# Charger_MCU_V01.net
KiCad netlist of a schematic drawn in Altium Designer
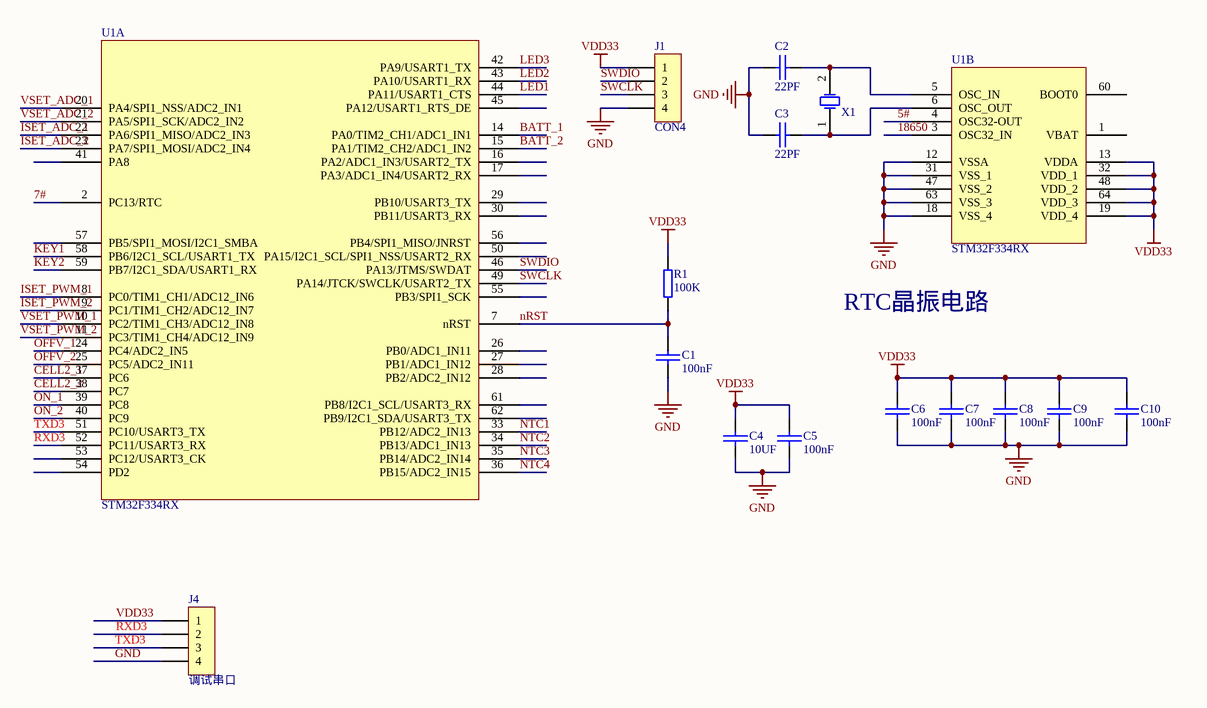
[diagram p0: Charger_MCU_V01.SchDoc]

(export (version "E")
  (design (tool "Eeschema 10.0.6"))
  (components
    (comp (ref "C1")
      (value "100nF")
      (footprint "C0603")
      (description "CAP CER 0.1UF 50V Y5V 0603")
      (fields
        (field (name "MANUFACTURER") "Yageo")
        (field (name "MANUFACTURER PART NUMBER") "CC0603ZRY5V9BB104")
      )
      (libsource (lib "电容") (part "C0603"))
    )
    (comp (ref "C2")
      (value "22PF")
      (footprint "C0603")
      (description "CAP CER 22PF 50V Y5V 0603")
      (fields (field (name "Comment") "C0603"))
      (libsource (lib "电容") (part "C0603"))
    )
    (comp (ref "C3")
      (value "22PF")
      (footprint "C0603")
      (description "CAP CER 22PF 50V Y5V 0603")
      (fields (field (name "Comment") "C0603"))
      (libsource (lib "电容") (part "C0603"))
    )
    (comp (ref "C4")
      (value "10UF")
      (footprint "C0603")
      (description "CAP CER 10UF 50V Y5V 0603")
      (fields
        (field (name "MANUFACTURER") "Yageo")
        (field (name "MANUFACTURER PART NUMBER") "CC0603ZRY5V9BB106")
      )
      (libsource (lib "电容") (part "C0603"))
    )
    (comp (ref "C5")
      (value "100nF")
      (footprint "C0603")
      (description "CAP CER 100nF 50V Y5V 0603")
      (fields
        (field (name "MANUFACTURER") "Yageo")
        (field (name "MANUFACTURER PART NUMBER") "CC0603ZRY5V9BB104")
      )
      (libsource (lib "电容") (part "C0603"))
    )
    (comp (ref "C6")
      (value "100nF")
      (footprint "C0603")
      (description "CAP CER 100nF 50V Y5V 0603")
      (fields
        (field (name "MANUFACTURER") "Yageo")
        (field (name "MANUFACTURER PART NUMBER") "CC0603ZRY5V9BB104")
      )
      (libsource (lib "电容") (part "C0603"))
    )
    (comp (ref "C7")
      (value "100nF")
      (footprint "C0603")
      (description "CAP CER 100nF 50V Y5V 0603")
      (fields
        (field (name "MANUFACTURER") "Yageo")
        (field (name "MANUFACTURER PART NUMBER") "CC0603ZRY5V9BB104")
      )
      (libsource (lib "电容") (part "C0603"))
    )
    (comp (ref "C8")
      (value "100nF")
      (footprint "C0603")
      (description "CAP CER 100nF 50V Y5V 0603")
      (fields
        (field (name "MANUFACTURER") "Yageo")
        (field (name "MANUFACTURER PART NUMBER") "CC0603ZRY5V9BB104")
      )
      (libsource (lib "电容") (part "C0603"))
    )
    (comp (ref "C9")
      (value "100nF")
      (footprint "C0603")
      (description "CAP CER 100nF 50V Y5V 0603")
      (fields
        (field (name "MANUFACTURER") "Yageo")
        (field (name "MANUFACTURER PART NUMBER") "CC0603ZRY5V9BB104")
      )
      (libsource (lib "电容") (part "C0603"))
    )
    (comp (ref "C10")
      (value "100nF")
      (footprint "C0603")
      (description "CAP CER 100nF 50V Y5V 0603")
      (fields
        (field (name "MANUFACTURER") "Yageo")
        (field (name "MANUFACTURER PART NUMBER") "CC0603ZRY5V9BB104")
      )
      (libsource (lib "电容") (part "C0603"))
    )
    (comp (ref "J1")
      (value "CON4")
      (footprint "SIP4")
      (description "2.54mm 程序下载口")
      (libsource (lib "") (part "CON4_1"))
    )
    (comp (ref "J4")
      (value "调试串口")
      (footprint "SIP4")
      (description "2.54mm dip")
      (libsource (lib "接插件") (part "CON4"))
    )
    (comp (ref "R1")
      (value "100K")
      (footprint "R0603")
      (description "RES 100K OHM 1/10W 5% 0603 SMD")
      (fields (field (name "MANUFACTURER") "Yageo") (field (name "Comment") "R0603"))
      (libsource (lib "电阻") (part "R0603"))
    )
    (comp (ref "U1")
      (value "STM32F334RX")
      (footprint "LQFP64")
      (description "MCU ARM 64KB FLASH MEM 64-LQFP")
      (fields
        (field (name "MANUFACTURER") "STMicroelectronics")
        (field (name "MANUFACTURER PART NUMBER") "STM32F103R8T6")
      )
      (libsource (lib "集成电路") (part "STM32F334RX"))
    )
    (comp (ref "X1")
      (value "9C-8.000MBBK-T")
      (footprint "XTAL2")
      (description "CRYSTAL 8.000MHZ 20PF SMD")
      (fields (field (name "MANUFACTURER") "TXC CORPORATION"))
      (libsource (lib "接插件") (part "CRYSTAL-XTAL2"))
    )
  )
  (nets
    (net (code "1") (name "/5#") (class "Default")
      (node (ref "U1") (pin "4") (pinfunction "OSC32-OUT_4") (pintype "passive"))
    )
    (net (code "2") (name "/7#") (class "Default")
      (node (ref "U1") (pin "2") (pinfunction "PC13/RTC_2") (pintype "passive"))
    )
    (net (code "3") (name "/18650") (class "Default")
      (node (ref "U1") (pin "3") (pinfunction "OSC32_IN_3") (pintype "passive"))
    )
    (net (code "4") (name "/BATT_1") (class "Default")
      (node (ref "U1") (pin "14") (pinfunction "PA0/TIM2_CH1/ADC1_IN1_14") (pintype "passive"))
    )
    (net (code "5") (name "/BATT_2") (class "Default")
      (node (ref "U1") (pin "15") (pinfunction "PA1/TIM2_CH2/ADC1_IN2_15") (pintype "passive"))
    )
    (net (code "6") (name "/CELL2_1") (class "Default")
      (node (ref "U1") (pin "37") (pinfunction "PC6_37") (pintype "passive"))
    )
    (net (code "7") (name "/CELL2_2") (class "Default")
      (node (ref "U1") (pin "38") (pinfunction "PC7_38") (pintype "passive"))
    )
    (net (code "8") (name "/ISET_ADC_1") (class "Default")
      (node (ref "U1") (pin "22") (pinfunction "PA6/SPI1_MISO/ADC2_IN3_22") (pintype "passive"))
    )
    (net (code "9") (name "/ISET_ADC_2") (class "Default")
      (node (ref "U1") (pin "23") (pinfunction "PA7/SPI1_MOSI/ADC2_IN4_23") (pintype "passive"))
    )
    (net (code "10") (name "/ISET_PWM_1") (class "Default")
      (node (ref "U1") (pin "8") (pinfunction "PC0/TIM1_CH1/ADC12_IN6_8") (pintype "passive"))
    )
    (net (code "11") (name "/ISET_PWM_2") (class "Default")
      (node (ref "U1") (pin "9") (pinfunction "PC1/TIM1_CH2/ADC12_IN7_9") (pintype "passive"))
    )
    (net (code "12") (name "/KEY1") (class "Default")
      (node (ref "U1") (pin "58") (pinfunction "PB6/I2C1_SCL/USART1_TX_58") (pintype "passive"))
    )
    (net (code "13") (name "/KEY2") (class "Default")
      (node (ref "U1") (pin "59") (pinfunction "PB7/I2C1_SDA/USART1_RX_59") (pintype "passive"))
    )
    (net (code "14") (name "/LED1") (class "Default")
      (node (ref "U1") (pin "44") (pinfunction "PA11/USART1_CTS_44") (pintype "passive"))
    )
    (net (code "15") (name "/LED2") (class "Default")
      (node (ref "U1") (pin "43") (pinfunction "PA10/USART1_RX_43") (pintype "passive"))
    )
    (net (code "16") (name "/LED3") (class "Default")
      (node (ref "U1") (pin "42") (pinfunction "PA9/USART1_TX_42") (pintype "passive"))
    )
    (net (code "17") (name "/NTC1") (class "Default")
      (node (ref "U1") (pin "33") (pinfunction "PB12/ADC2_IN13_33") (pintype "passive"))
    )
    (net (code "18") (name "/NTC2") (class "Default")
      (node (ref "U1") (pin "34") (pinfunction "PB13/ADC1_IN13_34") (pintype "passive"))
    )
    (net (code "19") (name "/NTC3") (class "Default")
      (node (ref "U1") (pin "35") (pinfunction "PB14/ADC2_IN14_35") (pintype "passive"))
    )
    (net (code "20") (name "/NTC4") (class "Default")
      (node (ref "U1") (pin "36") (pinfunction "PB15/ADC2_IN15_36") (pintype "passive"))
    )
    (net (code "21") (name "/OFFV_1") (class "Default")
      (node (ref "U1") (pin "24") (pinfunction "PC4/ADC2_IN5_24") (pintype "passive"))
    )
    (net (code "22") (name "/OFFV_2") (class "Default")
      (node (ref "U1") (pin "25") (pinfunction "PC5/ADC2_IN11_25") (pintype "passive"))
    )
    (net (code "23") (name "/ON_1") (class "Default")
      (node (ref "U1") (pin "39") (pinfunction "PC8_39") (pintype "passive"))
    )
    (net (code "24") (name "/ON_2") (class "Default")
      (node (ref "U1") (pin "40") (pinfunction "PC9_40") (pintype "passive"))
    )
    (net (code "25") (name "/RXD3") (class "Default")
      (node (ref "J4") (pin "2") (pinfunction "2_2") (pintype "passive"))
      (node (ref "U1") (pin "52") (pinfunction "PC11/USART3_RX_52") (pintype "passive"))
    )
    (net (code "26") (name "/SWCLK") (class "Default")
      (node (ref "J1") (pin "3") (pinfunction "3_3") (pintype "passive"))
      (node (ref "U1") (pin "49") (pinfunction "PA14/JTCK/SWCLK/USART2_TX_49") (pintype "passive"))
    )
    (net (code "27") (name "/SWDIO") (class "Default")
      (node (ref "J1") (pin "2") (pinfunction "2_2") (pintype "passive"))
      (node (ref "U1") (pin "46") (pinfunction "PA13/JTMS/SWDAT_46") (pintype "passive"))
    )
    (net (code "28") (name "/TXD3") (class "Default")
      (node (ref "J4") (pin "3") (pinfunction "3_3") (pintype "passive"))
      (node (ref "U1") (pin "51") (pinfunction "PC10/USART3_TX_51") (pintype "passive"))
    )
    (net (code "29") (name "/VSET_ADC_1") (class "Default")
      (node (ref "U1") (pin "20") (pinfunction "PA4/SPI1_NSS/ADC2_IN1_20") (pintype "passive"))
    )
    (net (code "30") (name "/VSET_ADC_2") (class "Default")
      (node (ref "U1") (pin "21") (pinfunction "PA5/SPI1_SCK/ADC2_IN2_21") (pintype "passive"))
    )
    (net (code "31") (name "/VSET_PWM_1") (class "Default")
      (node (ref "U1") (pin "10") (pinfunction "PC2/TIM1_CH3/ADC12_IN8_10") (pintype "passive"))
    )
    (net (code "32") (name "/VSET_PWM_2") (class "Default")
      (node (ref "U1") (pin "11") (pinfunction "PC3/TIM1_CH4/ADC12_IN9_11") (pintype "passive"))
    )
    (net (code "33") (name "/nRST") (class "Default")
      (node (ref "C1") (pin "1") (pinfunction "1_1") (pintype "passive"))
      (node (ref "R1") (pin "1") (pinfunction "1_1") (pintype "passive"))
      (node (ref "U1") (pin "7") (pinfunction "nRST_7") (pintype "passive"))
    )
    (net (code "34") (name "GND") (class "Default")
      (node (ref "C1") (pin "2") (pinfunction "2_2") (pintype "passive"))
      (node (ref "C10") (pin "2") (pinfunction "2_2") (pintype "passive"))
      (node (ref "C2") (pin "1") (pinfunction "1_1") (pintype "passive"))
      (node (ref "C3") (pin "1") (pinfunction "1_1") (pintype "passive"))
      (node (ref "C4") (pin "2") (pinfunction "2_2") (pintype "passive"))
      (node (ref "C5") (pin "2") (pinfunction "2_2") (pintype "passive"))
      (node (ref "C6") (pin "2") (pinfunction "2_2") (pintype "passive"))
      (node (ref "C7") (pin "2") (pinfunction "2_2") (pintype "passive"))
      (node (ref "C8") (pin "2") (pinfunction "2_2") (pintype "passive"))
      (node (ref "C9") (pin "2") (pinfunction "2_2") (pintype "passive"))
      (node (ref "J1") (pin "4") (pinfunction "4_4") (pintype "passive"))
      (node (ref "J4") (pin "4") (pinfunction "4_4") (pintype "passive"))
      (node (ref "U1") (pin "12") (pinfunction "VSSA_12") (pintype "passive"))
      (node (ref "U1") (pin "18") (pinfunction "VSS_4_18") (pintype "passive"))
      (node (ref "U1") (pin "31") (pinfunction "VSS_1_31") (pintype "passive"))
      (node (ref "U1") (pin "47") (pinfunction "VSS_2_47") (pintype "passive"))
      (node (ref "U1") (pin "63") (pinfunction "VSS_3_63") (pintype "passive"))
    )
    (net (code "35") (name "Net-(U1B-OSC_IN)") (class "Default")
      (node (ref "C2") (pin "2") (pinfunction "2_2") (pintype "passive"))
      (node (ref "U1") (pin "5") (pinfunction "OSC_IN_5") (pintype "passive"))
      (node (ref "X1") (pin "2") (pinfunction "OSC2_2") (pintype "passive"))
    )
    (net (code "36") (name "Net-(U1B-OSC_OUT)") (class "Default")
      (node (ref "C3") (pin "2") (pinfunction "2_2") (pintype "passive"))
      (node (ref "U1") (pin "6") (pinfunction "OSC_OUT_6") (pintype "passive"))
      (node (ref "X1") (pin "1") (pinfunction "OSC1_1") (pintype "passive"))
    )
    (net (code "37") (name "VDD33") (class "Default")
      (node (ref "C10") (pin "1") (pinfunction "1_1") (pintype "passive"))
      (node (ref "C4") (pin "1") (pinfunction "1_1") (pintype "passive"))
      (node (ref "C5") (pin "1") (pinfunction "1_1") (pintype "passive"))
      (node (ref "C6") (pin "1") (pinfunction "1_1") (pintype "passive"))
      (node (ref "C7") (pin "1") (pinfunction "1_1") (pintype "passive"))
      (node (ref "C8") (pin "1") (pinfunction "1_1") (pintype "passive"))
      (node (ref "C9") (pin "1") (pinfunction "1_1") (pintype "passive"))
      (node (ref "J1") (pin "1") (pinfunction "1_1") (pintype "passive"))
      (node (ref "J4") (pin "1") (pinfunction "1_1") (pintype "passive"))
      (node (ref "R1") (pin "2") (pinfunction "2_2") (pintype "passive"))
      (node (ref "U1") (pin "13") (pinfunction "VDDA_13") (pintype "passive"))
      (node (ref "U1") (pin "19") (pinfunction "VDD_4_19") (pintype "passive"))
      (node (ref "U1") (pin "32") (pinfunction "VDD_1_32") (pintype "passive"))
      (node (ref "U1") (pin "48") (pinfunction "VDD_2_48") (pintype "passive"))
      (node (ref "U1") (pin "64") (pinfunction "VDD_3_64") (pintype "passive"))
    )
    (net (code "38") (name "unconnected-(U1A-PA2{slash}ADC1_IN3{slash}USART2_TX-Pad16)") (class "Default")
      (node (ref "U1") (pin "16") (pinfunction "PA2/ADC1_IN3/USART2_TX_16") (pintype "passive"))
    )
    (net (code "39") (name "unconnected-(U1A-PA3{slash}ADC1_IN4{slash}USART2_RX-Pad17)") (class "Default")
      (node (ref "U1") (pin "17") (pinfunction "PA3/ADC1_IN4/USART2_RX_17") (pintype "passive"))
    )
    (net (code "40") (name "unconnected-(U1A-PA8-Pad41)") (class "Default")
      (node (ref "U1") (pin "41") (pinfunction "PA8_41") (pintype "passive"))
    )
    (net (code "41") (name "unconnected-(U1A-PA12{slash}USART1_RTS_DE-Pad45)") (class "Default")
      (node (ref "U1") (pin "45") (pinfunction "PA12/USART1_RTS_DE_45") (pintype "passive"))
    )
    (net (code "42") (name "unconnected-(U1A-PA15{slash}I2C1_SCL{slash}SPI1_NSS{slash}USART2_RX-Pad50)") (class "Default")
      (node (ref "U1") (pin "50") (pinfunction "PA15/I2C1_SCL/SPI1_NSS/USART2_RX_50") (pintype "passive"))
    )
    (net (code "43") (name "unconnected-(U1A-PB0{slash}ADC1_IN11-Pad26)") (class "Default")
      (node (ref "U1") (pin "26") (pinfunction "PB0/ADC1_IN11_26") (pintype "passive"))
    )
    (net (code "44") (name "unconnected-(U1A-PB1{slash}ADC1_IN12-Pad27)") (class "Default")
      (node (ref "U1") (pin "27") (pinfunction "PB1/ADC1_IN12_27") (pintype "passive"))
    )
    (net (code "45") (name "unconnected-(U1A-PB2{slash}ADC2_IN12-Pad28)") (class "Default")
      (node (ref "U1") (pin "28") (pinfunction "PB2/ADC2_IN12_28") (pintype "passive"))
    )
    (net (code "46") (name "unconnected-(U1A-PB3{slash}SPI1_SCK-Pad55)") (class "Default")
      (node (ref "U1") (pin "55") (pinfunction "PB3/SPI1_SCK_55") (pintype "passive"))
    )
    (net (code "47") (name "unconnected-(U1A-PB4{slash}SPI1_MISO{slash}JNRST-Pad56)") (class "Default")
      (node (ref "U1") (pin "56") (pinfunction "PB4/SPI1_MISO/JNRST_56") (pintype "passive"))
    )
    (net (code "48") (name "unconnected-(U1A-PB5{slash}SPI1_MOSI{slash}I2C1_SMBA-Pad57)") (class "Default")
      (node (ref "U1") (pin "57") (pinfunction "PB5/SPI1_MOSI/I2C1_SMBA_57") (pintype "passive"))
    )
    (net (code "49") (name "unconnected-(U1A-PB8{slash}I2C1_SCL{slash}USART3_RX-Pad61)") (class "Default")
      (node (ref "U1") (pin "61") (pinfunction "PB8/I2C1_SCL/USART3_RX_61") (pintype "passive"))
    )
    (net (code "50") (name "unconnected-(U1A-PB9{slash}I2C1_SDA{slash}USART3_TX-Pad62)") (class "Default")
      (node (ref "U1") (pin "62") (pinfunction "PB9/I2C1_SDA/USART3_TX_62") (pintype "passive"))
    )
    (net (code "51") (name "unconnected-(U1A-PB10{slash}USART3_TX-Pad29)") (class "Default")
      (node (ref "U1") (pin "29") (pinfunction "PB10/USART3_TX_29") (pintype "passive"))
    )
    (net (code "52") (name "unconnected-(U1A-PB11{slash}USART3_RX-Pad30)") (class "Default")
      (node (ref "U1") (pin "30") (pinfunction "PB11/USART3_RX_30") (pintype "passive"))
    )
    (net (code "53") (name "unconnected-(U1A-PC12{slash}USART3_CK-Pad53)") (class "Default")
      (node (ref "U1") (pin "53") (pinfunction "PC12/USART3_CK_53") (pintype "passive"))
    )
    (net (code "54") (name "unconnected-(U1A-PD2-Pad54)") (class "Default")
      (node (ref "U1") (pin "54") (pinfunction "PD2_54") (pintype "passive"))
    )
    (net (code "55") (name "unconnected-(U1B-BOOT0-Pad60)") (class "Default")
      (node (ref "U1") (pin "60") (pinfunction "BOOT0_60") (pintype "passive"))
    )
    (net (code "56") (name "unconnected-(U1B-VBAT-Pad1)") (class "Default")
      (node (ref "U1") (pin "1") (pinfunction "VBAT_1") (pintype "passive"))
    )
  )
)
